# TLC5951_TestBrd.net
KiCad netlist of a schematic drawn in EAGLE
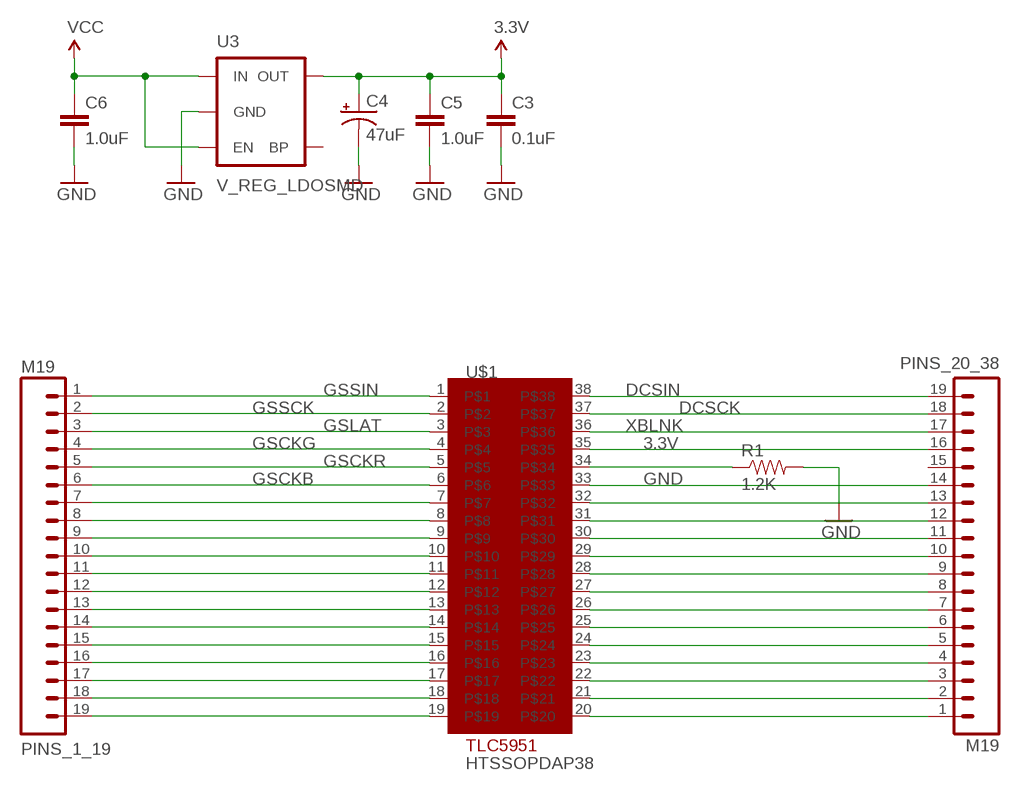
[diagram p0: schematic, sheet 1]

(export (version "E")
  (design (tool "Eeschema 10.0.6"))
  (components
    (comp (ref "C3")
      (value "0.1uF")
      (footprint "eagle-import:0402-CAP")
      (libsource (lib "eagle-import") (part "CAP0402-CAP"))
    )
    (comp (ref "C4")
      (value "47uF")
      (footprint "eagle-import:EIA3528")
      (libsource (lib "eagle-import") (part "CAP_POL3528"))
    )
    (comp (ref "C5")
      (value "1.0uF")
      (footprint "eagle-import:0402-CAP")
      (libsource (lib "eagle-import") (part "CAP0402-CAP"))
    )
    (comp (ref "C6")
      (value "1.0uF")
      (footprint "eagle-import:0402-CAP")
      (libsource (lib "eagle-import") (part "CAP0402-CAP"))
    )
    (comp (ref "PINS_1_19")
      (value "M19")
      (footprint "eagle-import:1X19")
      (libsource (lib "eagle-import") (part "M19"))
    )
    (comp (ref "PINS_20_38")
      (value "M19")
      (footprint "eagle-import:1X19")
      (libsource (lib "eagle-import") (part "M19"))
    )
    (comp (ref "R1")
      (value "1.2K")
      (footprint "eagle-import:AXIAL-0.6")
      (libsource (lib "eagle-import") (part "RESISTORPTH-1W"))
    )
    (comp (ref "U$1")
      (value "HTSSOPDAP38")
      (footprint "eagle-import:HTSSOPDAP38")
      (libsource (lib "eagle-import") (part "HTSSOPDAP38"))
    )
    (comp (ref "U3")
      (value "V_REG_LDOSMD")
      (footprint "eagle-import:SOT23-5")
      (libsource (lib "eagle-import") (part "V_REG_LDOSMD"))
    )
  )
  (nets
    (net (code "1") (name "/DCSCK") (class "Default")
      (node (ref "PINS_20_38") (pin "18") (pinfunction "18_18") (pintype "passive"))
      (node (ref "U$1") (pin "37") (pinfunction "P$37_37") (pintype "input"))
    )
    (net (code "2") (name "/DCSIN") (class "Default")
      (node (ref "PINS_20_38") (pin "19") (pinfunction "19_19") (pintype "passive"))
      (node (ref "U$1") (pin "38") (pinfunction "P$38_38") (pintype "input"))
    )
    (net (code "3") (name "/GSCKB") (class "Default")
      (node (ref "PINS_1_19") (pin "6") (pinfunction "6_6") (pintype "passive"))
      (node (ref "U$1") (pin "6") (pinfunction "P$6_6") (pintype "input"))
    )
    (net (code "4") (name "/GSCKG") (class "Default")
      (node (ref "PINS_1_19") (pin "4") (pinfunction "4_4") (pintype "passive"))
      (node (ref "U$1") (pin "4") (pinfunction "P$4_4") (pintype "input"))
    )
    (net (code "5") (name "/GSCKR") (class "Default")
      (node (ref "PINS_1_19") (pin "5") (pinfunction "5_5") (pintype "passive"))
      (node (ref "U$1") (pin "5") (pinfunction "P$5_5") (pintype "input"))
    )
    (net (code "6") (name "/GSLAT") (class "Default")
      (node (ref "PINS_1_19") (pin "3") (pinfunction "3_3") (pintype "passive"))
      (node (ref "U$1") (pin "3") (pinfunction "P$3_3") (pintype "input"))
    )
    (net (code "7") (name "/GSSCK") (class "Default")
      (node (ref "PINS_1_19") (pin "2") (pinfunction "2_2") (pintype "passive"))
      (node (ref "U$1") (pin "2") (pinfunction "P$2_2") (pintype "input"))
    )
    (net (code "8") (name "/GSSIN") (class "Default")
      (node (ref "PINS_1_19") (pin "1") (pinfunction "1_1") (pintype "passive"))
      (node (ref "U$1") (pin "1") (pinfunction "P$1_1") (pintype "input"))
    )
    (net (code "9") (name "/XBLNK") (class "Default")
      (node (ref "PINS_20_38") (pin "17") (pinfunction "17_17") (pintype "passive"))
      (node (ref "U$1") (pin "36") (pinfunction "P$36_36") (pintype "input"))
    )
    (net (code "10") (name "3.3V") (class "Default")
      (node (ref "C3") (pin "1") (pinfunction "1_1") (pintype "passive"))
      (node (ref "C4") (pin "A") (pinfunction "+_A") (pintype "passive"))
      (node (ref "C5") (pin "1") (pinfunction "1_1") (pintype "passive"))
      (node (ref "PINS_20_38") (pin "16") (pinfunction "16_16") (pintype "passive"))
      (node (ref "U$1") (pin "35") (pinfunction "P$35_35") (pintype "input"))
      (node (ref "U3") (pin "5") (pinfunction "OUT_5") (pintype "passive"))
    )
    (net (code "11") (name "GND") (class "Default")
      (node (ref "C3") (pin "2") (pinfunction "2_2") (pintype "passive"))
      (node (ref "C4") (pin "C") (pinfunction "-_C") (pintype "passive"))
      (node (ref "C5") (pin "2") (pinfunction "2_2") (pintype "passive"))
      (node (ref "C6") (pin "2") (pinfunction "2_2") (pintype "passive"))
      (node (ref "PINS_20_38") (pin "14") (pinfunction "14_14") (pintype "passive"))
      (node (ref "R1") (pin "P$2") (pinfunction "2_P$2") (pintype "passive"))
      (node (ref "U$1") (pin "33") (pinfunction "P$33_33") (pintype "input"))
      (node (ref "U3") (pin "2") (pinfunction "GND_2") (pintype "input"))
    )
    (net (code "12") (name "Net-(R1-1)") (class "Default")
      (node (ref "R1") (pin "P$1") (pinfunction "1_P$1") (pintype "passive"))
      (node (ref "U$1") (pin "34") (pinfunction "P$34_34") (pintype "input"))
    )
    (net (code "13") (name "Net-(U$1-P$7)") (class "Default")
      (node (ref "PINS_1_19") (pin "7") (pinfunction "7_7") (pintype "passive"))
      (node (ref "U$1") (pin "7") (pinfunction "P$7_7") (pintype "output"))
    )
    (net (code "14") (name "Net-(U$1-P$8)") (class "Default")
      (node (ref "PINS_1_19") (pin "8") (pinfunction "8_8") (pintype "passive"))
      (node (ref "U$1") (pin "8") (pinfunction "P$8_8") (pintype "output"))
    )
    (net (code "15") (name "Net-(U$1-P$9)") (class "Default")
      (node (ref "PINS_1_19") (pin "9") (pinfunction "9_9") (pintype "passive"))
      (node (ref "U$1") (pin "9") (pinfunction "P$9_9") (pintype "output"))
    )
    (net (code "16") (name "Net-(U$1-P$10)") (class "Default")
      (node (ref "PINS_1_19") (pin "10") (pinfunction "10_10") (pintype "passive"))
      (node (ref "U$1") (pin "10") (pinfunction "P$10_10") (pintype "output"))
    )
    (net (code "17") (name "Net-(U$1-P$11)") (class "Default")
      (node (ref "PINS_1_19") (pin "11") (pinfunction "11_11") (pintype "passive"))
      (node (ref "U$1") (pin "11") (pinfunction "P$11_11") (pintype "output"))
    )
    (net (code "18") (name "Net-(U$1-P$12)") (class "Default")
      (node (ref "PINS_1_19") (pin "12") (pinfunction "12_12") (pintype "passive"))
      (node (ref "U$1") (pin "12") (pinfunction "P$12_12") (pintype "output"))
    )
    (net (code "19") (name "Net-(U$1-P$13)") (class "Default")
      (node (ref "PINS_1_19") (pin "13") (pinfunction "13_13") (pintype "passive"))
      (node (ref "U$1") (pin "13") (pinfunction "P$13_13") (pintype "output"))
    )
    (net (code "20") (name "Net-(U$1-P$14)") (class "Default")
      (node (ref "PINS_1_19") (pin "14") (pinfunction "14_14") (pintype "passive"))
      (node (ref "U$1") (pin "14") (pinfunction "P$14_14") (pintype "output"))
    )
    (net (code "21") (name "Net-(U$1-P$15)") (class "Default")
      (node (ref "PINS_1_19") (pin "15") (pinfunction "15_15") (pintype "passive"))
      (node (ref "U$1") (pin "15") (pinfunction "P$15_15") (pintype "output"))
    )
    (net (code "22") (name "Net-(U$1-P$16)") (class "Default")
      (node (ref "PINS_1_19") (pin "16") (pinfunction "16_16") (pintype "passive"))
      (node (ref "U$1") (pin "16") (pinfunction "P$16_16") (pintype "output"))
    )
    (net (code "23") (name "Net-(U$1-P$17)") (class "Default")
      (node (ref "PINS_1_19") (pin "17") (pinfunction "17_17") (pintype "passive"))
      (node (ref "U$1") (pin "17") (pinfunction "P$17_17") (pintype "output"))
    )
    (net (code "24") (name "Net-(U$1-P$18)") (class "Default")
      (node (ref "PINS_1_19") (pin "18") (pinfunction "18_18") (pintype "passive"))
      (node (ref "U$1") (pin "18") (pinfunction "P$18_18") (pintype "output"))
    )
    (net (code "25") (name "Net-(U$1-P$19)") (class "Default")
      (node (ref "PINS_1_19") (pin "19") (pinfunction "19_19") (pintype "passive"))
      (node (ref "U$1") (pin "19") (pinfunction "P$19_19") (pintype "output"))
    )
    (net (code "26") (name "Net-(U$1-P$20)") (class "Default")
      (node (ref "PINS_20_38") (pin "1") (pinfunction "1_1") (pintype "passive"))
      (node (ref "U$1") (pin "20") (pinfunction "P$20_20") (pintype "output"))
    )
    (net (code "27") (name "Net-(U$1-P$21)") (class "Default")
      (node (ref "PINS_20_38") (pin "2") (pinfunction "2_2") (pintype "passive"))
      (node (ref "U$1") (pin "21") (pinfunction "P$21_21") (pintype "output"))
    )
    (net (code "28") (name "Net-(U$1-P$22)") (class "Default")
      (node (ref "PINS_20_38") (pin "3") (pinfunction "3_3") (pintype "passive"))
      (node (ref "U$1") (pin "22") (pinfunction "P$22_22") (pintype "output"))
    )
    (net (code "29") (name "Net-(U$1-P$23)") (class "Default")
      (node (ref "PINS_20_38") (pin "4") (pinfunction "4_4") (pintype "passive"))
      (node (ref "U$1") (pin "23") (pinfunction "P$23_23") (pintype "output"))
    )
    (net (code "30") (name "Net-(U$1-P$24)") (class "Default")
      (node (ref "PINS_20_38") (pin "5") (pinfunction "5_5") (pintype "passive"))
      (node (ref "U$1") (pin "24") (pinfunction "P$24_24") (pintype "output"))
    )
    (net (code "31") (name "Net-(U$1-P$25)") (class "Default")
      (node (ref "PINS_20_38") (pin "6") (pinfunction "6_6") (pintype "passive"))
      (node (ref "U$1") (pin "25") (pinfunction "P$25_25") (pintype "output"))
    )
    (net (code "32") (name "Net-(U$1-P$26)") (class "Default")
      (node (ref "PINS_20_38") (pin "7") (pinfunction "7_7") (pintype "passive"))
      (node (ref "U$1") (pin "26") (pinfunction "P$26_26") (pintype "output"))
    )
    (net (code "33") (name "Net-(U$1-P$27)") (class "Default")
      (node (ref "PINS_20_38") (pin "8") (pinfunction "8_8") (pintype "passive"))
      (node (ref "U$1") (pin "27") (pinfunction "P$27_27") (pintype "output"))
    )
    (net (code "34") (name "Net-(U$1-P$28)") (class "Default")
      (node (ref "PINS_20_38") (pin "9") (pinfunction "9_9") (pintype "passive"))
      (node (ref "U$1") (pin "28") (pinfunction "P$28_28") (pintype "output"))
    )
    (net (code "35") (name "Net-(U$1-P$29)") (class "Default")
      (node (ref "PINS_20_38") (pin "10") (pinfunction "10_10") (pintype "passive"))
      (node (ref "U$1") (pin "29") (pinfunction "P$29_29") (pintype "output"))
    )
    (net (code "36") (name "Net-(U$1-P$30)") (class "Default")
      (node (ref "PINS_20_38") (pin "11") (pinfunction "11_11") (pintype "passive"))
      (node (ref "U$1") (pin "30") (pinfunction "P$30_30") (pintype "output"))
    )
    (net (code "37") (name "Net-(U$1-P$31)") (class "Default")
      (node (ref "PINS_20_38") (pin "12") (pinfunction "12_12") (pintype "passive"))
      (node (ref "U$1") (pin "31") (pinfunction "P$31_31") (pintype "output"))
    )
    (net (code "38") (name "Net-(U$1-P$32)") (class "Default")
      (node (ref "PINS_20_38") (pin "13") (pinfunction "13_13") (pintype "passive"))
      (node (ref "U$1") (pin "32") (pinfunction "P$32_32") (pintype "output"))
    )
    (net (code "39") (name "VCC") (class "Default")
      (node (ref "C6") (pin "1") (pinfunction "1_1") (pintype "passive"))
      (node (ref "U3") (pin "1") (pinfunction "IN_1") (pintype "input"))
      (node (ref "U3") (pin "3") (pinfunction "EN_3") (pintype "input"))
    )
    (net (code "40") (name "unconnected-(PINS_20_38-Pad15)") (class "Default")
      (node (ref "PINS_20_38") (pin "15") (pinfunction "15_15") (pintype "passive"))
    )
    (net (code "41") (name "unconnected-(U3-BP-Pad4)") (class "Default")
      (node (ref "U3") (pin "4") (pinfunction "BP_4") (pintype "input"))
    )
  )
)
